# main.net
KiCad netlist of a schematic drawn in Altium Designer
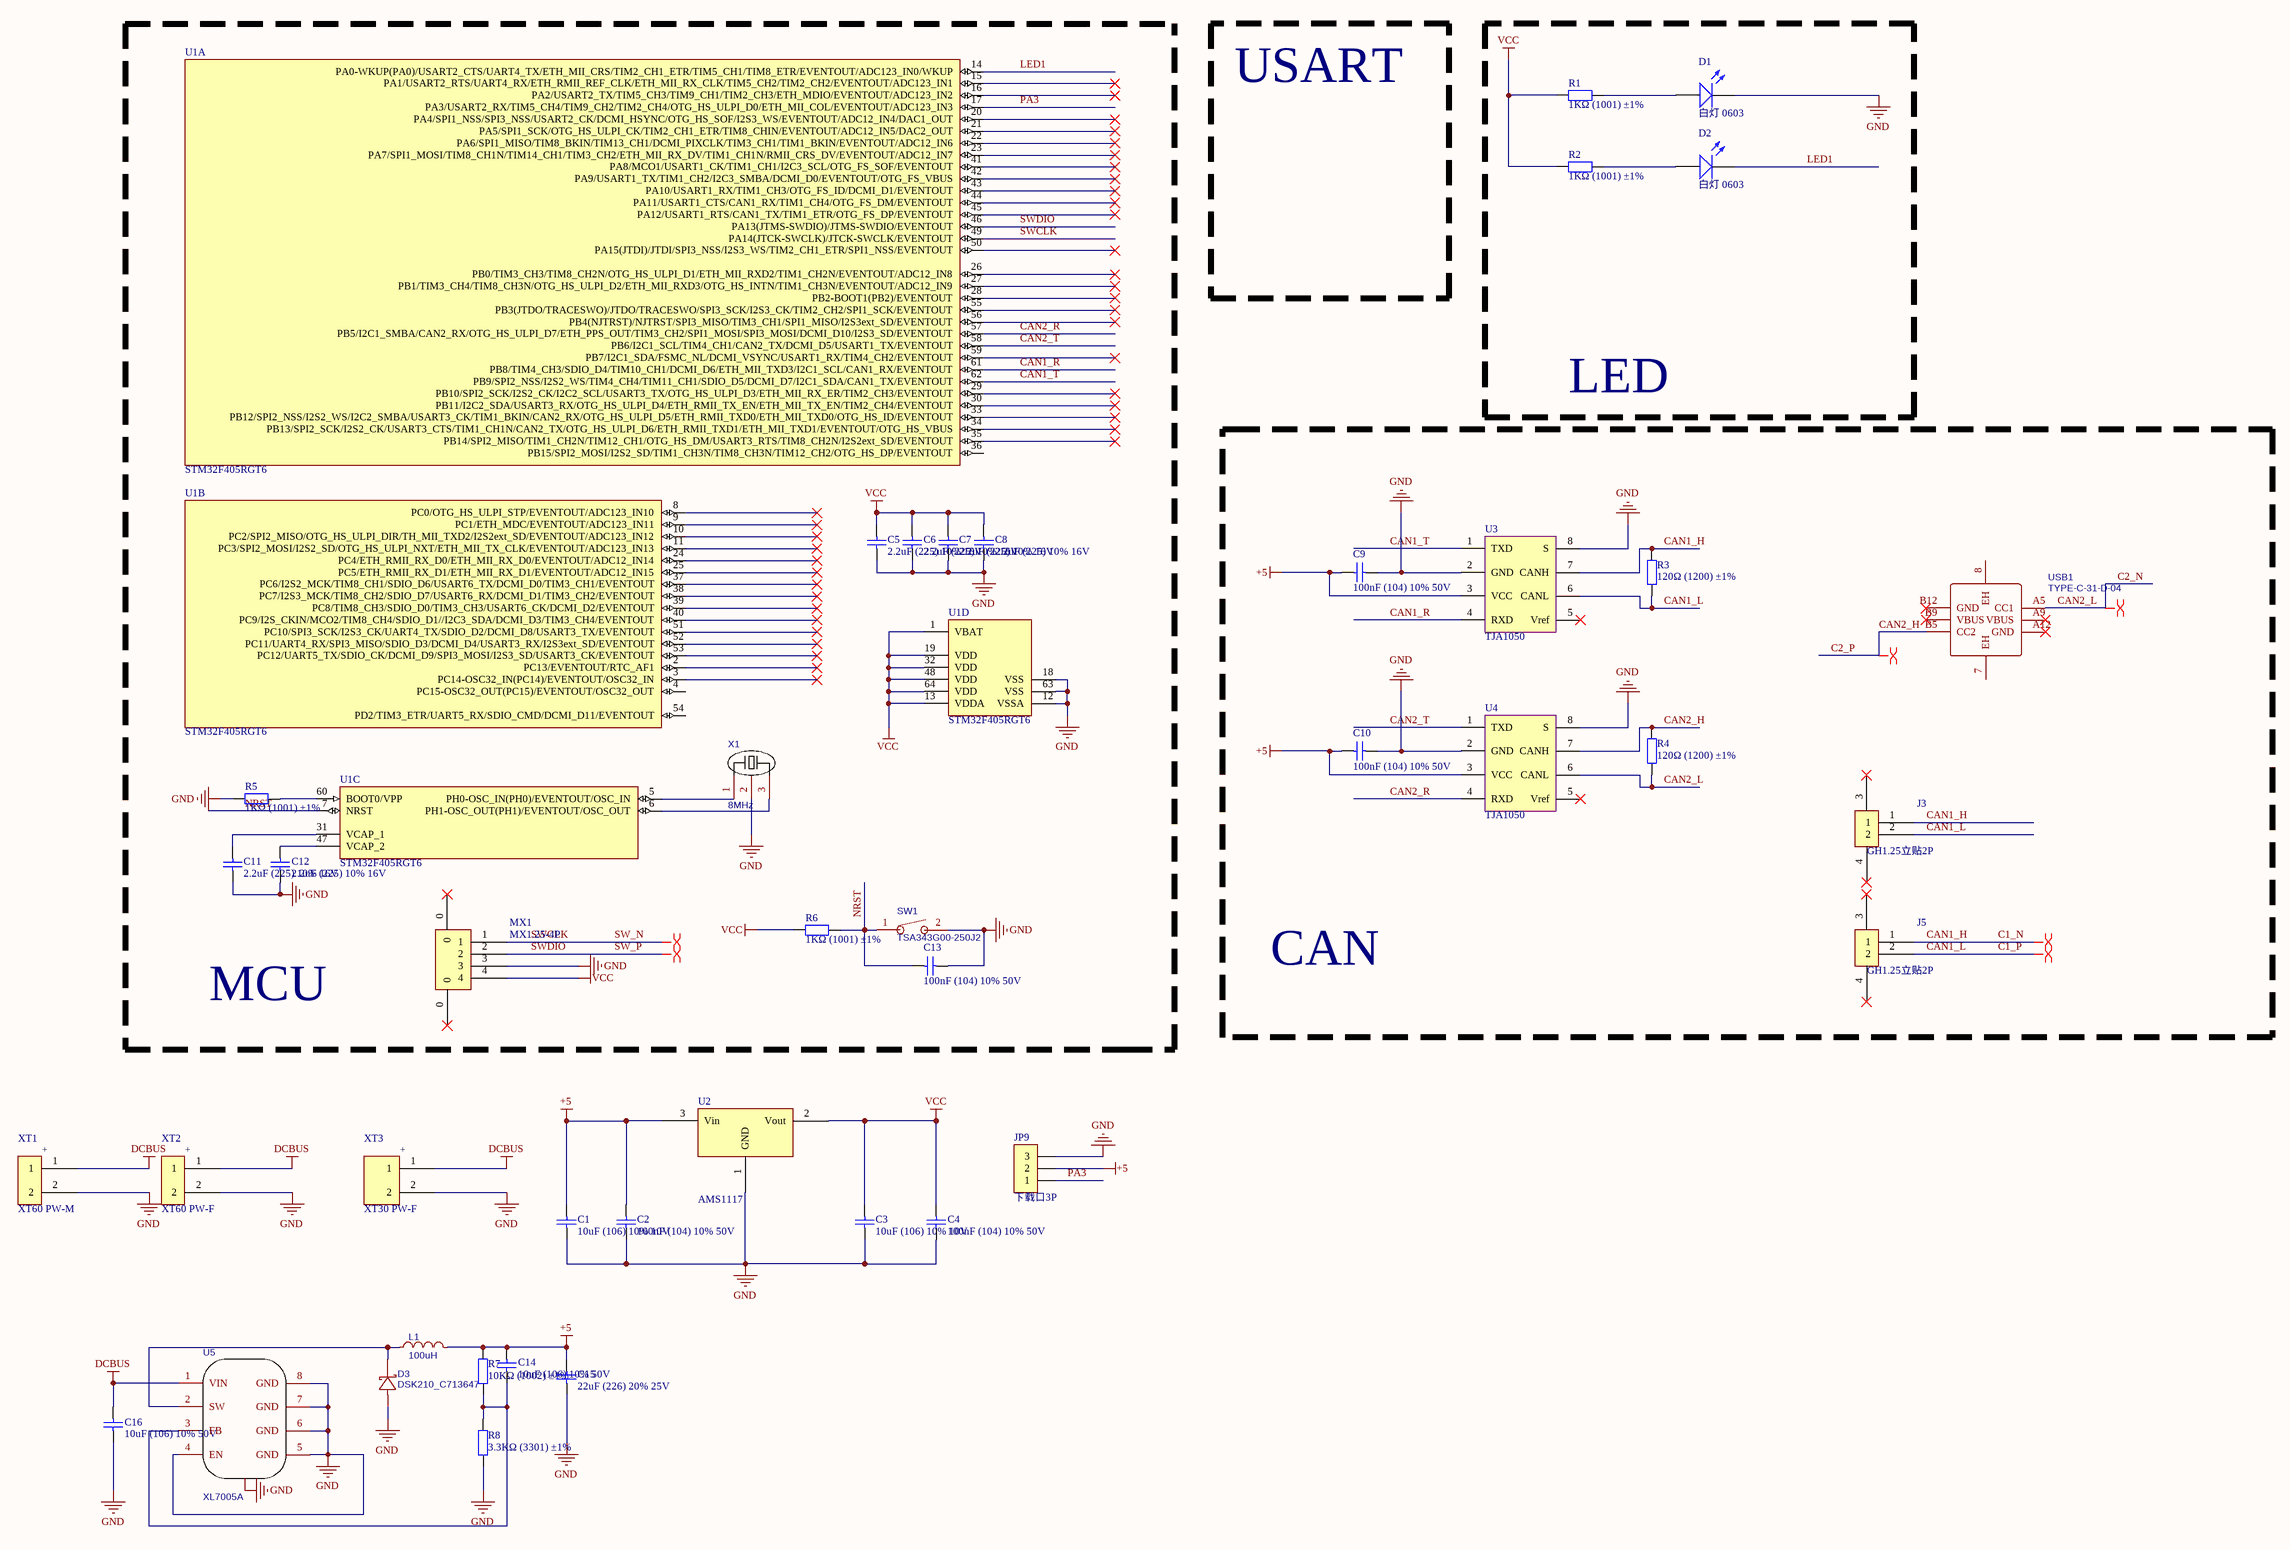
[diagram p0: main.SchDoc]

(export (version "E")
  (design (tool "Eeschema 10.0.6"))
  (components
    (comp (ref "C1")
      (value "10uF (106) 10% 10V")
      (footprint "0603_C")
      (description "贴片电容")
      (libsource (lib "Miscellaneous Devices LC") (part "0603 10uF (106) 10% 10V"))
    )
    (comp (ref "C2")
      (value "100nF (104) 10% 50V")
      (footprint "0603_C")
      (description "贴片电容")
      (libsource (lib "Miscellaneous Devices LC") (part "0603 100nF (104) 10% 50V"))
    )
    (comp (ref "C3")
      (value "10uF (106) 10% 10V")
      (footprint "0603_C")
      (description "贴片电容")
      (libsource (lib "Miscellaneous Devices LC") (part "0603 10uF (106) 10% 10V"))
    )
    (comp (ref "C4")
      (value "100nF (104) 10% 50V")
      (footprint "0603_C")
      (description "贴片电容")
      (libsource (lib "Miscellaneous Devices LC") (part "0603 100nF (104) 10% 50V"))
    )
    (comp (ref "C5")
      (value "2.2uF (225) 10% 16V")
      (footprint "0603_C")
      (description "贴片电容")
      (libsource (lib "Miscellaneous Devices LC") (part "0603 2.2uF (225) 10% 16V"))
    )
    (comp (ref "C6")
      (value "2.2uF (225) 10% 16V")
      (footprint "0603_C")
      (description "贴片电容")
      (libsource (lib "Miscellaneous Devices LC") (part "0603 2.2uF (225) 10% 16V"))
    )
    (comp (ref "C7")
      (value "2.2uF (225) 10% 16V")
      (footprint "0603_C")
      (description "贴片电容")
      (libsource (lib "Miscellaneous Devices LC") (part "0603 2.2uF (225) 10% 16V"))
    )
    (comp (ref "C8")
      (value "2.2uF (225) 10% 16V")
      (footprint "0603_C")
      (description "贴片电容")
      (libsource (lib "Miscellaneous Devices LC") (part "0603 2.2uF (225) 10% 16V"))
    )
    (comp (ref "C9")
      (value "100nF (104) 10% 50V")
      (footprint "0603_C")
      (description "贴片电容")
      (libsource (lib "Miscellaneous Devices LC") (part "0603 100nF (104) 10% 50V"))
    )
    (comp (ref "C10")
      (value "100nF (104) 10% 50V")
      (footprint "0603_C")
      (description "贴片电容")
      (libsource (lib "Miscellaneous Devices LC") (part "0603 100nF (104) 10% 50V"))
    )
    (comp (ref "C11")
      (value "2.2uF (225) 10% 16V")
      (footprint "0603_C")
      (description "贴片电容")
      (libsource (lib "Miscellaneous Devices LC") (part "0603 2.2uF (225) 10% 16V"))
    )
    (comp (ref "C12")
      (value "2.2uF (225) 10% 16V")
      (footprint "0603_C")
      (description "贴片电容")
      (libsource (lib "Miscellaneous Devices LC") (part "0603 2.2uF (225) 10% 16V"))
    )
    (comp (ref "C13")
      (value "100nF (104) 10% 50V")
      (footprint "0603_C")
      (description "贴片电容")
      (libsource (lib "Miscellaneous Devices LC") (part "0603 100nF (104) 10% 50V"))
    )
    (comp (ref "C14")
      (value "10uF (106) 10% 50V")
      (footprint "1206_C")
      (description "贴片电容")
      (libsource (lib "Miscellaneous Devices LC") (part "1206 10uF (106) 10% 50V"))
    )
    (comp (ref "C15")
      (value "22uF (226) 20% 25V")
      (footprint "0805_C")
      (description "贴片电容")
      (libsource (lib "Miscellaneous Devices LC") (part "0805 22uF (226) 20% 25V"))
    )
    (comp (ref "C16")
      (value "10uF (106) 10% 50V")
      (footprint "1206_C")
      (description "贴片电容")
      (libsource (lib "Miscellaneous Devices LC") (part "1206 10uF (106) 10% 50V"))
    )
    (comp (ref "D1")
      (value "白灯 0603")
      (footprint "0603_LED_S1")
      (description "发光二极管")
      (libsource (lib "Miscellaneous Devices LC") (part "0603 白灯"))
    )
    (comp (ref "D2")
      (value "白灯 0603")
      (footprint "0603_LED_S1")
      (description "发光二极管")
      (libsource (lib "Miscellaneous Devices LC") (part "0603 白灯"))
    )
    (comp (ref "D3")
      (value "DSK210_C713647")
      (footprint "SOD-123FL_L2.7-W1.8-LS3.8-RD")
      (fields
        (field (name "BOM_SUPPLIER PART") "C713647")
        (field (name "BOM_MANUFACTURER PART") "DSK210")
        (field (name "CONTRIBUTOR") "LCSC")
      )
      (libsource (lib "MyLib") (part "DSK210_C713647"))
    )
    (comp (ref "J3")
      (value "GH1.25立贴2P")
      (footprint "CONN-SMD_2P-V-P1.25-L_X1251WVS-02HF-LPSW")
      (libsource (lib "MyLib") (part "GH1.25立贴2P"))
    )
    (comp (ref "J5")
      (value "GH1.25立贴2P")
      (footprint "CONN-SMD_2P-V-P1.25-L_X1251WVS-02HF-LPSW")
      (libsource (lib "MyLib") (part "GH1.25立贴2P"))
    )
    (comp (ref "JP9")
      (value "下载口3P")
      (footprint "GH1.25-WS-3P")
      (description "下载口3P SWD")
      (libsource (lib "0.0 - YltsSchlib") (part "接插件-下载口3P"))
    )
    (comp (ref "L1")
      (value "100uH")
      (footprint "IND-SMD_L3.5-W3.0_SLF0302")
      (fields
        (field (name "BOM_MANUFACTURER PART") "SLF0302-101KTT")
        (field (name "BOM_SUPPLIER PART") "C182197")
        (field (name "CONTRIBUTOR") "LCSC")
      )
      (libsource (lib "MyLib") (part "100uH"))
    )
    (comp (ref "MX1")
      (value "MX1.25-4P")
      (footprint "CONN-SMD_4P-1.25P_1.25T-4P")
      (libsource (lib "MyLib") (part "MX1.25-4P"))
    )
    (comp (ref "R1")
      (value "1KΩ (1001) ±1%")
      (footprint "0603_R")
      (description "贴片电阻")
      (libsource (lib "Miscellaneous Devices LC") (part "0603 1KΩ (1001) 1%"))
    )
    (comp (ref "R2")
      (value "1KΩ (1001) ±1%")
      (footprint "0603_R")
      (description "贴片电阻")
      (libsource (lib "Miscellaneous Devices LC") (part "0603 1KΩ (1001) 1%"))
    )
    (comp (ref "R3")
      (value "120Ω (1200) ±1%")
      (footprint "0603_R")
      (description "贴片电阻")
      (libsource (lib "Miscellaneous Devices LC") (part "0603 120Ω (1200) 1%"))
    )
    (comp (ref "R4")
      (value "120Ω (1200) ±1%")
      (footprint "0603_R")
      (description "贴片电阻")
      (libsource (lib "Miscellaneous Devices LC") (part "0603 120Ω (1200) 1%"))
    )
    (comp (ref "R5")
      (value "1KΩ (1001) ±1%")
      (footprint "0603_R")
      (description "贴片电阻")
      (libsource (lib "Miscellaneous Devices LC") (part "0603 1KΩ (1001) 1%"))
    )
    (comp (ref "R6")
      (value "1KΩ (1001) ±1%")
      (footprint "0603_R")
      (description "贴片电阻")
      (libsource (lib "Miscellaneous Devices LC") (part "0603 1KΩ (1001) 1%"))
    )
    (comp (ref "R7")
      (value "10KΩ (1002) ±1%")
      (footprint "0603_R")
      (description "贴片电阻")
      (libsource (lib "Miscellaneous Devices LC") (part "0603 10KΩ (1002) 1%"))
    )
    (comp (ref "R8")
      (value "3.3KΩ (3301) ±1%")
      (footprint "0603_R")
      (description "贴片电阻")
      (libsource (lib "Miscellaneous Devices LC") (part "0603 3.3KΩ (3301) 1%"))
    )
    (comp (ref "SW1")
      (value "TSA343G00-250J2")
      (footprint "SW-SMD_L4.0-W2.9-LS5.0")
      (description "贴片轻触开关")
      (fields (field (name "BOM_SUPPLIER PART") "C354946") (field (name "CONTRIBUTOR") "LCSC"))
      (libsource (lib "MyLib") (part "TSA343G00-250J2"))
    )
    (comp (ref "U1")
      (value "STM32F405RGT6")
      (footprint "TQFP64_M")
      (libsource (lib "MyLib") (part "STM32F405RGT6"))
    )
    (comp (ref "U2")
      (value "AMS1117")
      (footprint "SOT-223_L6.7-W3.5-P2.30-BR")
      (libsource (lib "MyLib") (part "AMS1117"))
    )
    (comp (ref "U3")
      (value "TJA1050")
      (footprint "SOIC-8_L5.0-W4.0-P1.27-LS6.0-BL")
      (libsource (lib "未分类IC") (part "TJA1050"))
    )
    (comp (ref "U4")
      (value "TJA1050")
      (footprint "SOIC-8_L5.0-W4.0-P1.27-LS6.0-BL")
      (libsource (lib "未分类IC") (part "TJA1050"))
    )
    (comp (ref "U5")
      (value "XL7005A")
      (footprint "SOIC-8_L5.0-W4.0-P1.27-LS6.0-BL-EP2.0")
      (fields (field (name "BOM_SUPPLIER PART") "C50848"))
      (libsource (lib "MyLib") (part "XL7005A"))
    )
    (comp (ref "USB1")
      (value "TYPE-C-31-D-04")
      (footprint "TYPE-C-SMD_TYPE-C-31-D-04")
      (fields (field (name "BOM_SUPPLIER PART") "C840347") (field (name "CONTRIBUTOR") "LCSC"))
      (libsource (lib "MyLib") (part "TYPE-C-31-D-04"))
    )
    (comp (ref "X1")
      (value "8MHz")
      (footprint "OSC-SMD_3P-L3.2-W1.3-P1.2-L")
      (fields
        (field (name "BOM_MANUFACTURER PART") "CSTCE8M00G15C99-R0")
        (field (name "BOM_SUPPLIER PART") "C110614")
      )
      (libsource (lib "MyLib") (part "8MHz-3P"))
    )
    (comp (ref "XT1")
      (value "XT60 PW-M")
      (footprint "XT60 PW-M")
      (libsource (lib "MyLib") (part "XT60 PW-M"))
    )
    (comp (ref "XT2")
      (value "XT60 PW-F")
      (footprint "XT60 PW-F")
      (libsource (lib "MyLib") (part "XT60 PW-F"))
    )
    (comp (ref "XT3")
      (value "XT30 PW-F")
      (footprint "XT30 PW-F")
      (libsource (lib "MyLib") (part "XT30 PW-F"))
    )
  )
  (nets
    (net (code "1") (name "+5") (class "Default")
      (node (ref "C1") (pin "2") (pinfunction "2_2") (pintype "passive"))
      (node (ref "C10") (pin "2") (pinfunction "2_2") (pintype "passive"))
      (node (ref "C14") (pin "2") (pinfunction "2_2") (pintype "passive"))
      (node (ref "C15") (pin "2") (pinfunction "2_2") (pintype "passive"))
      (node (ref "C2") (pin "1") (pinfunction "1_1") (pintype "passive"))
      (node (ref "C9") (pin "2") (pinfunction "2_2") (pintype "passive"))
      (node (ref "JP9") (pin "2") (pinfunction "2_2") (pintype "passive"))
      (node (ref "L1") (pin "2") (pinfunction "2_2") (pintype "passive"))
      (node (ref "R7") (pin "2") (pinfunction "2_2") (pintype "passive"))
      (node (ref "U2") (pin "3") (pinfunction "Vin_3") (pintype "passive"))
      (node (ref "U3") (pin "3") (pinfunction "VCC_3") (pintype "passive"))
      (node (ref "U4") (pin "3") (pinfunction "VCC_3") (pintype "passive"))
    )
    (net (code "2") (name "/C1_N") (class "Default")
      (node (ref "J3") (pin "1") (pinfunction "1_1") (pintype "passive"))
      (node (ref "J5") (pin "1") (pinfunction "1_1") (pintype "passive"))
      (node (ref "R3") (pin "2") (pinfunction "2_2") (pintype "passive"))
      (node (ref "U3") (pin "7") (pinfunction "CANH_7") (pintype "passive"))
    )
    (net (code "3") (name "/C1_P") (class "Default")
      (node (ref "J3") (pin "2") (pinfunction "2_2") (pintype "passive"))
      (node (ref "J5") (pin "2") (pinfunction "2_2") (pintype "passive"))
      (node (ref "R3") (pin "1") (pinfunction "1_1") (pintype "passive"))
      (node (ref "U3") (pin "6") (pinfunction "CANL_6") (pintype "passive"))
    )
    (net (code "4") (name "/C2_N") (class "Default")
      (node (ref "R4") (pin "1") (pinfunction "1_1") (pintype "passive"))
      (node (ref "U4") (pin "6") (pinfunction "CANL_6") (pintype "passive"))
      (node (ref "USB1") (pin "A5") (pinfunction "CC1_A5") (pintype "passive"))
    )
    (net (code "5") (name "/C2_P") (class "Default")
      (node (ref "R4") (pin "2") (pinfunction "2_2") (pintype "passive"))
      (node (ref "U4") (pin "7") (pinfunction "CANH_7") (pintype "passive"))
      (node (ref "USB1") (pin "B5") (pinfunction "CC2_B5") (pintype "passive"))
    )
    (net (code "6") (name "/CAN1_R") (class "Default")
      (node (ref "U1") (pin "61") (pinfunction "PB8/TIM4_CH3/SDIO_D4/TIM10_CH1/DCMI_D6/ETH_MII_TXD3/I2C1_SCL/CAN1_RX/EVENTOUT_61") (pintype "bidirectional"))
      (node (ref "U3") (pin "4") (pinfunction "RXD_4") (pintype "passive"))
    )
    (net (code "7") (name "/CAN1_T") (class "Default")
      (node (ref "U1") (pin "62") (pinfunction "PB9/SPI2_NSS/I2S2_WS/TIM4_CH4/TIM11_CH1/SDIO_D5/DCMI_D7/I2C1_SDA/CAN1_TX/EVENTOUT_62") (pintype "bidirectional"))
      (node (ref "U3") (pin "1") (pinfunction "TXD_1") (pintype "passive"))
    )
    (net (code "8") (name "/CAN2_R") (class "Default")
      (node (ref "U1") (pin "57") (pinfunction "PB5/I2C1_SMBA/CAN2_RX/OTG_HS_ULPI_D7/ETH_PPS_OUT/TIM3_CH2/SPI1_MOSI/SPI3_MOSI/DCMI_D10/I2S3_SD/EVENTOUT_57") (pintype "bidirectional"))
      (node (ref "U4") (pin "4") (pinfunction "RXD_4") (pintype "passive"))
    )
    (net (code "9") (name "/CAN2_T") (class "Default")
      (node (ref "U1") (pin "58") (pinfunction "PB6/I2C1_SCL/TIM4_CH1/CAN2_TX/DCMI_D5/USART1_TX/EVENTOUT_58") (pintype "bidirectional"))
      (node (ref "U4") (pin "1") (pinfunction "TXD_1") (pintype "passive"))
    )
    (net (code "10") (name "/LED1") (class "Default")
      (node (ref "D2") (pin "K") (pinfunction "K_K") (pintype "passive"))
      (node (ref "U1") (pin "14") (pinfunction "PA0-WKUP(PA0)/USART2_CTS/UART4_TX/ETH_MII_CRS/TIM2_CH1_ETR/TIM5_CH1/TIM8_ETR/EVENTOUT/ADC123_IN0/WKUP_14") (pintype "bidirectional"))
    )
    (net (code "11") (name "/NRST") (class "Default")
      (node (ref "C13") (pin "2") (pinfunction "2_2") (pintype "passive"))
      (node (ref "R6") (pin "2") (pinfunction "2_2") (pintype "passive"))
      (node (ref "SW1") (pin "1") (pinfunction "1_1") (pintype "passive"))
      (node (ref "U1") (pin "7") (pinfunction "NRST_7") (pintype "bidirectional"))
    )
    (net (code "12") (name "/PA3") (class "Default")
      (node (ref "JP9") (pin "1") (pinfunction "1_1") (pintype "passive"))
      (node (ref "U1") (pin "17") (pinfunction "PA3/USART2_RX/TIM5_CH4/TIM9_CH2/TIM2_CH4/OTG_HS_ULPI_D0/ETH_MII_COL/EVENTOUT/ADC123_IN3_17") (pintype "bidirectional"))
    )
    (net (code "13") (name "/SWCLK") (class "Default")
      (node (ref "MX1") (pin "1") (pinfunction "1_1") (pintype "passive"))
      (node (ref "U1") (pin "49") (pinfunction "PA14(JTCK-SWCLK)/JTCK-SWCLK/EVENTOUT_49") (pintype "bidirectional"))
    )
    (net (code "14") (name "/SWDIO") (class "Default")
      (node (ref "MX1") (pin "2") (pinfunction "2_2") (pintype "passive"))
      (node (ref "U1") (pin "46") (pinfunction "PA13(JTMS-SWDIO)/JTMS-SWDIO/EVENTOUT_46") (pintype "bidirectional"))
    )
    (net (code "15") (name "DCBUS") (class "Default")
      (node (ref "C16") (pin "2") (pinfunction "2_2") (pintype "passive"))
      (node (ref "U5") (pin "1") (pinfunction "VIN_1") (pintype "passive"))
      (node (ref "XT1") (pin "1") (pinfunction "1_1") (pintype "passive"))
      (node (ref "XT2") (pin "1") (pinfunction "1_1") (pintype "passive"))
      (node (ref "XT3") (pin "1") (pinfunction "1_1") (pintype "passive"))
    )
    (net (code "16") (name "GND") (class "Default")
      (node (ref "C1") (pin "1") (pinfunction "1_1") (pintype "passive"))
      (node (ref "C10") (pin "1") (pinfunction "1_1") (pintype "passive"))
      (node (ref "C11") (pin "1") (pinfunction "1_1") (pintype "passive"))
      (node (ref "C12") (pin "1") (pinfunction "1_1") (pintype "passive"))
      (node (ref "C13") (pin "1") (pinfunction "1_1") (pintype "passive"))
      (node (ref "C15") (pin "1") (pinfunction "1_1") (pintype "passive"))
      (node (ref "C16") (pin "1") (pinfunction "1_1") (pintype "passive"))
      (node (ref "C2") (pin "2") (pinfunction "2_2") (pintype "passive"))
      (node (ref "C3") (pin "1") (pinfunction "1_1") (pintype "passive"))
      (node (ref "C4") (pin "2") (pinfunction "2_2") (pintype "passive"))
      (node (ref "C5") (pin "1") (pinfunction "1_1") (pintype "passive"))
      (node (ref "C6") (pin "1") (pinfunction "1_1") (pintype "passive"))
      (node (ref "C7") (pin "1") (pinfunction "1_1") (pintype "passive"))
      (node (ref "C8") (pin "1") (pinfunction "1_1") (pintype "passive"))
      (node (ref "C9") (pin "1") (pinfunction "1_1") (pintype "passive"))
      (node (ref "D1") (pin "K") (pinfunction "K_K") (pintype "passive"))
      (node (ref "D3") (pin "2") (pinfunction "A_2") (pintype "passive"))
      (node (ref "JP9") (pin "3") (pinfunction "3_3") (pintype "passive"))
      (node (ref "MX1") (pin "3") (pinfunction "3_3") (pintype "passive"))
      (node (ref "R5") (pin "1") (pinfunction "1_1") (pintype "passive"))
      (node (ref "R8") (pin "1") (pinfunction "1_1") (pintype "passive"))
      (node (ref "SW1") (pin "2") (pinfunction "2_2") (pintype "passive"))
      (node (ref "U1") (pin "12") (pinfunction "VSSA_12") (pintype "power_in"))
      (node (ref "U1") (pin "18") (pinfunction "VSS_18") (pintype "power_in"))
      (node (ref "U1") (pin "63") (pinfunction "VSS_63") (pintype "power_in"))
      (node (ref "U2") (pin "1") (pinfunction "GND_1") (pintype "passive"))
      (node (ref "U3") (pin "2") (pinfunction "GND_2") (pintype "passive"))
      (node (ref "U3") (pin "8") (pinfunction "S_8") (pintype "passive"))
      (node (ref "U4") (pin "2") (pinfunction "GND_2") (pintype "passive"))
      (node (ref "U4") (pin "8") (pinfunction "S_8") (pintype "passive"))
      (node (ref "U5") (pin "4") (pinfunction "EN_4") (pintype "passive"))
      (node (ref "U5") (pin "5") (pinfunction "GND_5") (pintype "passive"))
      (node (ref "U5") (pin "6") (pinfunction "GND_6") (pintype "passive"))
      (node (ref "U5") (pin "7") (pinfunction "GND_7") (pintype "passive"))
      (node (ref "U5") (pin "8") (pinfunction "GND_8") (pintype "passive"))
      (node (ref "U5") (pin "9") (pinfunction "9_9") (pintype "passive"))
      (node (ref "X1") (pin "2") (pinfunction "2_2") (pintype "passive"))
      (node (ref "XT1") (pin "2") (pinfunction "2_2") (pintype "passive"))
      (node (ref "XT2") (pin "2") (pinfunction "2_2") (pintype "passive"))
      (node (ref "XT3") (pin "2") (pinfunction "2_2") (pintype "passive"))
    )
    (net (code "17") (name "Net-(D1-PadA)") (class "Default")
      (node (ref "D1") (pin "A") (pinfunction "A_A") (pintype "passive"))
      (node (ref "R1") (pin "2") (pinfunction "2_2") (pintype "passive"))
    )
    (net (code "18") (name "Net-(D2-PadA)") (class "Default")
      (node (ref "D2") (pin "A") (pinfunction "A_A") (pintype "passive"))
      (node (ref "R2") (pin "2") (pinfunction "2_2") (pintype "passive"))
    )
    (net (code "19") (name "Net-(D3-C)") (class "Default")
      (node (ref "D3") (pin "1") (pinfunction "C_1") (pintype "passive"))
      (node (ref "L1") (pin "1") (pinfunction "1_1") (pintype "passive"))
      (node (ref "U5") (pin "2") (pinfunction "SW_2") (pintype "passive"))
    )
    (net (code "20") (name "Net-(U1C-BOOT0{slash}VPP)") (class "Default")
      (node (ref "R5") (pin "2") (pinfunction "2_2") (pintype "passive"))
      (node (ref "U1") (pin "60") (pinfunction "BOOT0/VPP_60") (pintype "input"))
    )
    (net (code "21") (name "Net-(U1C-PH0-OSC_IN(PH0){slash}EVENTOUT{slash}OSC_IN)") (class "Default")
      (node (ref "U1") (pin "5") (pinfunction "PH0-OSC_IN(PH0)/EVENTOUT/OSC_IN_5") (pintype "bidirectional"))
      (node (ref "X1") (pin "1") (pinfunction "1_1") (pintype "passive"))
    )
    (net (code "22") (name "Net-(U1C-PH1-OSC_OUT(PH1){slash}EVENTOUT{slash}OSC_OUT)") (class "Default")
      (node (ref "U1") (pin "6") (pinfunction "PH1-OSC_OUT(PH1)/EVENTOUT/OSC_OUT_6") (pintype "bidirectional"))
      (node (ref "X1") (pin "3") (pinfunction "3_3") (pintype "passive"))
    )
    (net (code "23") (name "Net-(U1C-VCAP_1)") (class "Default")
      (node (ref "C11") (pin "2") (pinfunction "2_2") (pintype "passive"))
      (node (ref "U1") (pin "31") (pinfunction "VCAP_1_31") (pintype "power_in"))
    )
    (net (code "24") (name "Net-(U1C-VCAP_2)") (class "Default")
      (node (ref "C12") (pin "2") (pinfunction "2_2") (pintype "passive"))
      (node (ref "U1") (pin "47") (pinfunction "VCAP_2_47") (pintype "power_in"))
    )
    (net (code "25") (name "Net-(U5-FB)") (class "Default")
      (node (ref "C14") (pin "1") (pinfunction "1_1") (pintype "passive"))
      (node (ref "R7") (pin "1") (pinfunction "1_1") (pintype "passive"))
      (node (ref "R8") (pin "2") (pinfunction "2_2") (pintype "passive"))
      (node (ref "U5") (pin "3") (pinfunction "FB_3") (pintype "passive"))
    )
    (net (code "26") (name "VCC") (class "Default")
      (node (ref "C3") (pin "2") (pinfunction "2_2") (pintype "passive"))
      (node (ref "C4") (pin "1") (pinfunction "1_1") (pintype "passive"))
      (node (ref "C5") (pin "2") (pinfunction "2_2") (pintype "passive"))
      (node (ref "C6") (pin "2") (pinfunction "2_2") (pintype "passive"))
      (node (ref "C7") (pin "2") (pinfunction "2_2") (pintype "passive"))
      (node (ref "C8") (pin "2") (pinfunction "2_2") (pintype "passive"))
      (node (ref "MX1") (pin "4") (pinfunction "4_4") (pintype "passive"))
      (node (ref "R1") (pin "1") (pinfunction "1_1") (pintype "passive"))
      (node (ref "R2") (pin "1") (pinfunction "1_1") (pintype "passive"))
      (node (ref "R6") (pin "1") (pinfunction "1_1") (pintype "passive"))
      (node (ref "U1") (pin "1") (pinfunction "VBAT_1") (pintype "power_in"))
      (node (ref "U1") (pin "13") (pinfunction "VDDA_13") (pintype "power_in"))
      (node (ref "U1") (pin "19") (pinfunction "VDD_19") (pintype "power_in"))
      (node (ref "U1") (pin "32") (pinfunction "VDD_32") (pintype "power_in"))
      (node (ref "U1") (pin "48") (pinfunction "VDD_48") (pintype "power_in"))
      (node (ref "U1") (pin "64") (pinfunction "VDD_64") (pintype "power_in"))
      (node (ref "U2") (pin "2") (pinfunction "Vout_2") (pintype "passive"))
    )
    (net (code "27") (name "unconnected-(J3-Pad3)") (class "Default")
      (node (ref "J3") (pin "3") (pintype "passive+no_connect"))
    )
    (net (code "28") (name "unconnected-(J3-Pad4)") (class "Default")
      (node (ref "J3") (pin "4") (pintype "passive+no_connect"))
    )
    (net (code "29") (name "unconnected-(J5-Pad3)") (class "Default")
      (node (ref "J5") (pin "3") (pintype "passive+no_connect"))
    )
    (net (code "30") (name "unconnected-(J5-Pad4)") (class "Default")
      (node (ref "J5") (pin "4") (pintype "passive+no_connect"))
    )
    (net (code "31") (name "unconnected-(MX1-Pad0)") (class "Default")
      (node (ref "MX1") (pin "0") (pinfunction "0_0") (pintype "passive+no_connect"))
    )
    (net (code "32") (name "unconnected-(MX1-Pad0)_1") (class "Default")
      (node (ref "MX1") (pin "0") (pinfunction "0_0") (pintype "passive+no_connect"))
    )
    (net (code "33") (name "unconnected-(U1A-PA1{slash}USART2_RTS{slash}UART4_RX{slash}ETH_RMII_REF_CLK{slash}ETH_MII_RX_CLK{slash}TIM5_CH2{slash}TIM2_CH2{slash}EVENTOUT{slash}ADC123_IN1-Pad15)") (class "Default")
      (node (ref "U1") (pin "15") (pinfunction "PA1/USART2_RTS/UART4_RX/ETH_RMII_REF_CLK/ETH_MII_RX_CLK/TIM5_CH2/TIM2_CH2/EVENTOUT/ADC123_IN1_15") (pintype "bidirectional+no_connect"))
    )
    (net (code "34") (name "unconnected-(U1A-PA2{slash}USART2_TX{slash}TIM5_CH3{slash}TIM9_CH1{slash}TIM2_CH3{slash}ETH_MDIO{slash}EVENTOUT{slash}ADC123_IN2-Pad16)") (class "Default")
      (node (ref "U1") (pin "16") (pinfunction "PA2/USART2_TX/TIM5_CH3/TIM9_CH1/TIM2_CH3/ETH_MDIO/EVENTOUT/ADC123_IN2_16") (pintype "bidirectional+no_connect"))
    )
    (net (code "35") (name "unconnected-(U1A-PA4{slash}SPI1_NSS{slash}SPI3_NSS{slash}USART2_CK{slash}DCMI_HSYNC{slash}OTG_HS_SOF{slash}I2S3_WS{slash}EVENTOUT{slash}ADC12_IN4{slash}DAC1_OUT-Pad20)") (class "Default")
      (node (ref "U1") (pin "20") (pinfunction "PA4/SPI1_NSS/SPI3_NSS/USART2_CK/DCMI_HSYNC/OTG_HS_SOF/I2S3_WS/EVENTOUT/ADC12_IN4/DAC1_OUT_20") (pintype "bidirectional+no_connect"))
    )
    (net (code "36") (name "unconnected-(U1A-PA5{slash}SPI1_SCK{slash}OTG_HS_ULPI_CK{slash}TIM2_CH1_ETR{slash}TIM8_CHIN{slash}EVENTOUT{slash}ADC12_IN5{slash}DAC2_OUT-Pad21)") (class "Default")
      (node (ref "U1") (pin "21") (pinfunction "PA5/SPI1_SCK/OTG_HS_ULPI_CK/TIM2_CH1_ETR/TIM8_CHIN/EVENTOUT/ADC12_IN5/DAC2_OUT_21") (pintype "bidirectional+no_connect"))
    )
    (net (code "37") (name "unconnected-(U1A-PA6{slash}SPI1_MISO{slash}TIM8_BKIN{slash}TIM13_CH1{slash}DCMI_PIXCLK{slash}TIM3_CH1{slash}TIM1_BKIN{slash}EVENTOUT{slash}ADC12_IN6-Pad22)") (class "Default")
      (node (ref "U1") (pin "22") (pinfunction "PA6/SPI1_MISO/TIM8_BKIN/TIM13_CH1/DCMI_PIXCLK/TIM3_CH1/TIM1_BKIN/EVENTOUT/ADC12_IN6_22") (pintype "bidirectional+no_connect"))
    )
    (net (code "38") (name "unconnected-(U1A-PA7{slash}SPI1_MOSI{slash}TIM8_CH1N{slash}TIM14_CH1{slash}TIM3_CH2{slash}ETH_MII_RX_DV{slash}TIM1_CH1N{slash}RMII_CRS_DV{slash}EVENTOUT{slash}ADC12_IN7-Pad23)") (class "Default")
      (node (ref "U1") (pin "23") (pinfunction "PA7/SPI1_MOSI/TIM8_CH1N/TIM14_CH1/TIM3_CH2/ETH_MII_RX_DV/TIM1_CH1N/RMII_CRS_DV/EVENTOUT/ADC12_IN7_23") (pintype "bidirectional+no_connect"))
    )
    (net (code "39") (name "unconnected-(U1A-PA8{slash}MCO1{slash}USART1_CK{slash}TIM1_CH1{slash}I2C3_SCL{slash}OTG_FS_SOF{slash}EVENTOUT-Pad41)") (class "Default")
      (node (ref "U1") (pin "41") (pinfunction "PA8/MCO1/USART1_CK/TIM1_CH1/I2C3_SCL/OTG_FS_SOF/EVENTOUT_41") (pintype "bidirectional+no_connect"))
    )
    (net (code "40") (name "unconnected-(U1A-PA9{slash}USART1_TX{slash}TIM1_CH2{slash}I2C3_SMBA{slash}DCMI_D0{slash}EVENTOUT{slash}OTG_FS_VBUS-Pad42)") (class "Default")
      (node (ref "U1") (pin "42") (pinfunction "PA9/USART1_TX/TIM1_CH2/I2C3_SMBA/DCMI_D0/EVENTOUT/OTG_FS_VBUS_42") (pintype "bidirectional+no_connect"))
    )
    (net (code "41") (name "unconnected-(U1A-PA10{slash}USART1_RX{slash}TIM1_CH3{slash}OTG_FS_ID{slash}DCMI_D1{slash}EVENTOUT-Pad43)") (class "Default")
      (node (ref "U1") (pin "43") (pinfunction "PA10/USART1_RX/TIM1_CH3/OTG_FS_ID/DCMI_D1/EVENTOUT_43") (pintype "bidirectional+no_connect"))
    )
    (net (code "42") (name "unconnected-(U1A-PA11{slash}USART1_CTS{slash}CAN1_RX{slash}TIM1_CH4{slash}OTG_FS_DM{slash}EVENTOUT-Pad44)") (class "Default")
      (node (ref "U1") (pin "44") (pinfunction "PA11/USART1_CTS/CAN1_RX/TIM1_CH4/OTG_FS_DM/EVENTOUT_44") (pintype "bidirectional+no_connect"))
    )
    (net (code "43") (name "unconnected-(U1A-PA12{slash}USART1_RTS{slash}CAN1_TX{slash}TIM1_ETR{slash}OTG_FS_DP{slash}EVENTOUT-Pad45)") (class "Default")
      (node (ref "U1") (pin "45") (pinfunction "PA12/USART1_RTS/CAN1_TX/TIM1_ETR/OTG_FS_DP/EVENTOUT_45") (pintype "bidirectional+no_connect"))
    )
    (net (code "44") (name "unconnected-(U1A-PA15(JTDI){slash}JTDI{slash}SPI3_NSS{slash}I2S3_WS{slash}TIM2_CH1_ETR{slash}SPI1_NSS{slash}EVENTOUT-Pad50)") (class "Default")
      (node (ref "U1") (pin "50") (pinfunction "PA15(JTDI)/JTDI/SPI3_NSS/I2S3_WS/TIM2_CH1_ETR/SPI1_NSS/EVENTOUT_50") (pintype "bidirectional+no_connect"))
    )
    (net (code "45") (name "unconnected-(U1A-PB0{slash}TIM3_CH3{slash}TIM8_CH2N{slash}OTG_HS_ULPI_D1{slash}ETH_MII_RXD2{slash}TIM1_CH2N{slash}EVENTOUT{slash}ADC12_IN8-Pad26)") (class "Default")
      (node (ref "U1") (pin "26") (pinfunction "PB0/TIM3_CH3/TIM8_CH2N/OTG_HS_ULPI_D1/ETH_MII_RXD2/TIM1_CH2N/EVENTOUT/ADC12_IN8_26") (pintype "bidirectional+no_connect"))
    )
    (net (code "46") (name "unconnected-(U1A-PB1{slash}TIM3_CH4{slash}TIM8_CH3N{slash}OTG_HS_ULPI_D2{slash}ETH_MII_RXD3{slash}OTG_HS_INTN{slash}TIM1_CH3N{slash}EVENTOUT{slash}ADC12_IN9-Pad27)") (class "Default")
      (node (ref "U1") (pin "27") (pinfunction "PB1/TIM3_CH4/TIM8_CH3N/OTG_HS_ULPI_D2/ETH_MII_RXD3/OTG_HS_INTN/TIM1_CH3N/EVENTOUT/ADC12_IN9_27") (pintype "bidirectional+no_connect"))
    )
    (net (code "47") (name "unconnected-(U1A-PB2-BOOT1(PB2){slash}EVENTOUT-Pad28)") (class "Default")
      (node (ref "U1") (pin "28") (pinfunction "PB2-BOOT1(PB2)/EVENTOUT_28") (pintype "bidirectional+no_connect"))
    )
    (net (code "48") (name "unconnected-(U1A-PB3(JTDO{slash}TRACESWO){slash}JTDO{slash}TRACESWO{slash}SPI3_SCK{slash}I2S3_CK{slash}TIM2_CH2{slash}SPI1_SCK{slash}EVENTOUT-Pad55)") (class "Default")
      (node (ref "U1") (pin "55") (pinfunction "PB3(JTDO/TRACESWO)/JTDO/TRACESWO/SPI3_SCK/I2S3_CK/TIM2_CH2/SPI1_SCK/EVENTOUT_55") (pintype "bidirectional+no_connect"))
    )
    (net (code "49") (name "unconnected-(U1A-PB4(NJTRST){slash}NJTRST{slash}SPI3_MISO{slash}TIM3_CH1{slash}SPI1_MISO{slash}I2S3ext_SD{slash}EVENTOUT-Pad56)") (class "Default")
      (node (ref "U1") (pin "56") (pinfunction "PB4(NJTRST)/NJTRST/SPI3_MISO/TIM3_CH1/SPI1_MISO/I2S3ext_SD/EVENTOUT_56") (pintype "bidirectional+no_connect"))
    )
    (net (code "50") (name "unconnected-(U1A-PB7{slash}I2C1_SDA{slash}FSMC_NL{slash}DCMI_VSYNC{slash}USART1_RX{slash}TIM4_CH2{slash}EVENTOUT-Pad59)") (class "Default")
      (node (ref "U1") (pin "59") (pinfunction "PB7/I2C1_SDA/FSMC_NL/DCMI_VSYNC/USART1_RX/TIM4_CH2/EVENTOUT_59") (pintype "bidirectional+no_connect"))
    )
    (net (code "51") (name "unconnected-(U1A-PB10{slash}SPI2_SCK{slash}I2S2_CK{slash}I2C2_SCL{slash}USART3_TX{slash}OTG_HS_ULPI_D3{slash}ETH_MII_RX_ER{slash}TIM2_CH3{slash}EVENTOUT-Pad29)") (class "Default")
      (node (ref "U1") (pin "29") (pinfunction "PB10/SPI2_SCK/I2S2_CK/I2C2_SCL/USART3_TX/OTG_HS_ULPI_D3/ETH_MII_RX_ER/TIM2_CH3/EVENTOUT_29") (pintype "bidirectional+no_connect"))
    )
    (net (code "52") (name "unconnected-(U1A-PB11{slash}I2C2_SDA{slash}USART3_RX{slash}OTG_HS_ULPI_D4{slash}ETH_RMII_TX_EN{slash}ETH_MII_TX_EN{slash}TIM2_CH4{slash}EVENTOUT-Pad30)") (class "Default")
      (node (ref "U1") (pin "30") (pinfunction "PB11/I2C2_SDA/USART3_RX/OTG_HS_ULPI_D4/ETH_RMII_TX_EN/ETH_MII_TX_EN/TIM2_CH4/EVENTOUT_30") (pintype "bidirectional+no_connect"))
    )
    (net (code "53") (name "unconnected-(U1A-PB12{slash}SPI2_NSS{slash}I2S2_WS{slash}I2C2_SMBA{slash}USART3_CK{slash}TIM1_BKIN{slash}CAN2_RX{slash}OTG_HS_ULPI_D5{slash}ETH_RMII_TXD0{slash}ETH_MII_TXD0{slash}OTG_HS_ID{slash}EVENTOUT-Pad33)") (class "Default")
      (node (ref "U1") (pin "33") (pinfunction "PB12/SPI2_NSS/I2S2_WS/I2C2_SMBA/USART3_CK/TIM1_BKIN/CAN2_RX/OTG_HS_ULPI_D5/ETH_RMII_TXD0/ETH_MII_TXD0/OTG_HS_ID/EVENTOUT_33") (pintype "bidirectional+no_connect"))
    )
    (net (code "54") (name "unconnected-(U1A-PB13{slash}SPI2_SCK{slash}I2S2_CK{slash}USART3_CTS{slash}TIM1_CH1N{slash}CAN2_TX{slash}OTG_HS_ULPI_D6{slash}ETH_RMII_TXD1{slash}ETH_MII_TXD1{slash}EVENTOUT{slash}OTG_HS_VBUS-Pad34)") (class "Default")
      (node (ref "U1") (pin "34") (pinfunction "PB13/SPI2_SCK/I2S2_CK/USART3_CTS/TIM1_CH1N/CAN2_TX/OTG_HS_ULPI_D6/ETH_RMII_TXD1/ETH_MII_TXD1/EVENTOUT/OTG_HS_VBUS_34") (pintype "bidirectional+no_connect"))
    )
    (net (code "55") (name "unconnected-(U1A-PB14{slash}SPI2_MISO{slash}TIM1_CH2N{slash}TIM12_CH1{slash}OTG_HS_DM{slash}USART3_RTS{slash}TIM8_CH2N{slash}I2S2ext_SD{slash}EVENTOUT-Pad35)") (class "Default")
      (node (ref "U1") (pin "35") (pinfunction "PB14/SPI2_MISO/TIM1_CH2N/TIM12_CH1/OTG_HS_DM/USART3_RTS/TIM8_CH2N/I2S2ext_SD/EVENTOUT_35") (pintype "bidirectional+no_connect"))
    )
    (net (code "56") (name "unconnected-(U1A-PB15{slash}SPI2_MOSI{slash}I2S2_SD{slash}TIM1_CH3N{slash}TIM8_CH3N{slash}TIM12_CH2{slash}OTG_HS_DP{slash}EVENTOUT-Pad36)") (class "Default")
      (node (ref "U1") (pin "36") (pinfunction "PB15/SPI2_MOSI/I2S2_SD/TIM1_CH3N/TIM8_CH3N/TIM12_CH2/OTG_HS_DP/EVENTOUT_36") (pintype "bidirectional"))
    )
    (net (code "57") (name "unconnected-(U1B-PC0{slash}OTG_HS_ULPI_STP{slash}EVENTOUT{slash}ADC123_IN10-Pad8)") (class "Default")
      (node (ref "U1") (pin "8") (pinfunction "PC0/OTG_HS_ULPI_STP/EVENTOUT/ADC123_IN10_8") (pintype "bidirectional+no_connect"))
    )
    (net (code "58") (name "unconnected-(U1B-PC1{slash}ETH_MDC{slash}EVENTOUT{slash}ADC123_IN11-Pad9)") (class "Default")
      (node (ref "U1") (pin "9") (pinfunction "PC1/ETH_MDC/EVENTOUT/ADC123_IN11_9") (pintype "bidirectional+no_connect"))
    )
    (net (code "59") (name "unconnected-(U1B-PC2{slash}SPI2_MISO{slash}OTG_HS_ULPI_DIR{slash}TH_MII_TXD2{slash}I2S2ext_SD{slash}EVENTOUT{slash}ADC123_IN12-Pad10)") (class "Default")
      (node (ref "U1") (pin "10") (pinfunction "PC2/SPI2_MISO/OTG_HS_ULPI_DIR/TH_MII_TXD2/I2S2ext_SD/EVENTOUT/ADC123_IN12_10") (pintype "bidirectional+no_connect"))
    )
    (net (code "60") (name "unconnected-(U1B-PC3{slash}SPI2_MOSI{slash}I2S2_SD{slash}OTG_HS_ULPI_NXT{slash}ETH_MII_TX_CLK{slash}EVENTOUT{slash}ADC123_IN13-Pad11)") (class "Default")
      (node (ref "U1") (pin "11") (pinfunction "PC3/SPI2_MOSI/I2S2_SD/OTG_HS_ULPI_NXT/ETH_MII_TX_CLK/EVENTOUT/ADC123_IN13_11") (pintype "bidirectional+no_connect"))
    )
    (net (code "61") (name "unconnected-(U1B-PC4{slash}ETH_RMII_RX_D0{slash}ETH_MII_RX_D0{slash}EVENTOUT{slash}ADC12_IN14-Pad24)") (class "Default")
      (node (ref "U1") (pin "24") (pinfunction "PC4/ETH_RMII_RX_D0/ETH_MII_RX_D0/EVENTOUT/ADC12_IN14_24") (pintype "bidirectional+no_connect"))
    )
    (net (code "62") (name "unconnected-(U1B-PC5{slash}ETH_RMII_RX_D1{slash}ETH_MII_RX_D1{slash}EVENTOUT{slash}ADC12_IN15-Pad25)") (class "Default")
      (node (ref "U1") (pin "25") (pinfunction "PC5/ETH_RMII_RX_D1/ETH_MII_RX_D1/EVENTOUT/ADC12_IN15_25") (pintype "bidirectional+no_connect"))
    )
    (net (code "63") (name "unconnected-(U1B-PC6{slash}I2S2_MCK{slash}TIM8_CH1{slash}SDIO_D6{slash}USART6_TX{slash}DCMI_D0{slash}TIM3_CH1{slash}EVENTOUT-Pad37)") (class "Default")
      (node (ref "U1") (pin "37") (pinfunction "PC6/I2S2_MCK/TIM8_CH1/SDIO_D6/USART6_TX/DCMI_D0/TIM3_CH1/EVENTOUT_37") (pintype "bidirectional+no_connect"))
    )
    (net (code "64") (name "unconnected-(U1B-PC7{slash}I2S3_MCK{slash}TIM8_CH2{slash}SDIO_D7{slash}USART6_RX{slash}DCMI_D1{slash}TIM3_CH2{slash}EVENTOUT-Pad38)") (class "Default")
      (node (ref "U1") (pin "38") (pinfunction "PC7/I2S3_MCK/TIM8_CH2/SDIO_D7/USART6_RX/DCMI_D1/TIM3_CH2/EVENTOUT_38") (pintype "bidirectional+no_connect"))
    )
    (net (code "65") (name "unconnected-(U1B-PC8{slash}TIM8_CH3{slash}SDIO_D0{slash}TIM3_CH3{slash}USART6_CK{slash}DCMI_D2{slash}EVENTOUT-Pad39)") (class "Default")
      (node (ref "U1") (pin "39") (pinfunction "PC8/TIM8_CH3/SDIO_D0/TIM3_CH3/USART6_CK/DCMI_D2/EVENTOUT_39") (pintype "bidirectional+no_connect"))
    )
    (net (code "66") (name "unconnected-(U1B-PC9{slash}I2S_CKIN{slash}MCO2{slash}TIM8_CH4{slash}SDIO_D1{slash}{slash}I2C3_SDA{slash}DCMI_D3{slash}TIM3_CH4{slash}EVENTOUT-Pad40)") (class "Default")
      (node (ref "U1") (pin "40") (pinfunction "PC9/I2S_CKIN/MCO2/TIM8_CH4/SDIO_D1//I2C3_SDA/DCMI_D3/TIM3_CH4/EVENTOUT_40") (pintype "bidirectional+no_connect"))
    )
    (net (code "67") (name "unconnected-(U1B-PC10{slash}SPI3_SCK{slash}I2S3_CK{slash}UART4_TX{slash}SDIO_D2{slash}DCMI_D8{slash}USART3_TX{slash}EVENTOUT-Pad51)") (class "Default")
      (node (ref "U1") (pin "51") (pinfunction "PC10/SPI3_SCK/I2S3_CK/UART4_TX/SDIO_D2/DCMI_D8/USART3_TX/EVENTOUT_51") (pintype "bidirectional+no_connect"))
    )
    (net (code "68") (name "unconnected-(U1B-PC11{slash}UART4_RX{slash}SPI3_MISO{slash}SDIO_D3{slash}DCMI_D4{slash}USART3_RX{slash}I2S3ext_SD{slash}EVENTOUT-Pad52)") (class "Default")
      (node (ref "U1") (pin "52") (pinfunction "PC11/UART4_RX/SPI3_MISO/SDIO_D3/DCMI_D4/USART3_RX/I2S3ext_SD/EVENTOUT_52") (pintype "bidirectional+no_connect"))
    )
    (net (code "69") (name "unconnected-(U1B-PC12{slash}UART5_TX{slash}SDIO_CK{slash}DCMI_D9{slash}SPI3_MOSI{slash}I2S3_SD{slash}USART3_CK{slash}EVENTOUT-Pad53)") (class "Default")
      (node (ref "U1") (pin "53") (pinfunction "PC12/UART5_TX/SDIO_CK/DCMI_D9/SPI3_MOSI/I2S3_SD/USART3_CK/EVENTOUT_53") (pintype "bidirectional+no_connect"))
    )
    (net (code "70") (name "unconnected-(U1B-PC13{slash}EVENTOUT{slash}RTC_AF1-Pad2)") (class "Default")
      (node (ref "U1") (pin "2") (pinfunction "PC13/EVENTOUT/RTC_AF1_2") (pintype "bidirectional+no_connect"))
    )
    (net (code "71") (name "unconnected-(U1B-PC14-OSC32_IN(PC14){slash}EVENTOUT{slash}OSC32_IN-Pad3)") (class "Default")
      (node (ref "U1") (pin "3") (pinfunction "PC14-OSC32_IN(PC14)/EVENTOUT/OSC32_IN_3") (pintype "bidirectional+no_connect"))
    )
    (net (code "72") (name "unconnected-(U1B-PC15-OSC32_OUT(PC15){slash}EVENTOUT{slash}OSC32_OUT-Pad4)") (class "Default")
      (node (ref "U1") (pin "4") (pinfunction "PC15-OSC32_OUT(PC15)/EVENTOUT/OSC32_OUT_4") (pintype "bidirectional"))
    )
    (net (code "73") (name "unconnected-(U1B-PD2{slash}TIM3_ETR{slash}UART5_RX{slash}SDIO_CMD{slash}DCMI_D11{slash}EVENTOUT-Pad54)") (class "Default")
      (node (ref "U1") (pin "54") (pinfunction "PD2/TIM3_ETR/UART5_RX/SDIO_CMD/DCMI_D11/EVENTOUT_54") (pintype "bidirectional"))
    )
    (net (code "74") (name "unconnected-(U3-Vref-Pad5)") (class "Default")
      (node (ref "U3") (pin "5") (pinfunction "Vref_5") (pintype "passive+no_connect"))
    )
    (net (code "75") (name "unconnected-(U4-Vref-Pad5)") (class "Default")
      (node (ref "U4") (pin "5") (pinfunction "Vref_5") (pintype "passive+no_connect"))
    )
    (net (code "76") (name "unconnected-(USB1-EH-Pad7)") (class "Default")
      (node (ref "USB1") (pin "7") (pinfunction "EH_7") (pintype "passive"))
    )
    (net (code "77") (name "unconnected-(USB1-EH-Pad8)") (class "Default")
      (node (ref "USB1") (pin "8") (pinfunction "EH_8") (pintype "passive"))
    )
    (net (code "78") (name "unconnected-(USB1-GND-PadA12)") (class "Default")
      (node (ref "USB1") (pin "A12") (pinfunction "GND_A12") (pintype "passive+no_connect"))
    )
    (net (code "79") (name "unconnected-(USB1-GND-PadB12)") (class "Default")
      (node (ref "USB1") (pin "B12") (pinfunction "GND_B12") (pintype "passive+no_connect"))
    )
    (net (code "80") (name "unconnected-(USB1-VBUS-PadA9)") (class "Default")
      (node (ref "USB1") (pin "A9") (pinfunction "VBUS_A9") (pintype "passive+no_connect"))
    )
    (net (code "81") (name "unconnected-(USB1-VBUS-PadB9)") (class "Default")
      (node (ref "USB1") (pin "B9") (pinfunction "VBUS_B9") (pintype "passive+no_connect"))
    )
  )
)
